# OUT_MOT.net
KiCad netlist of a schematic drawn in Altium Designer
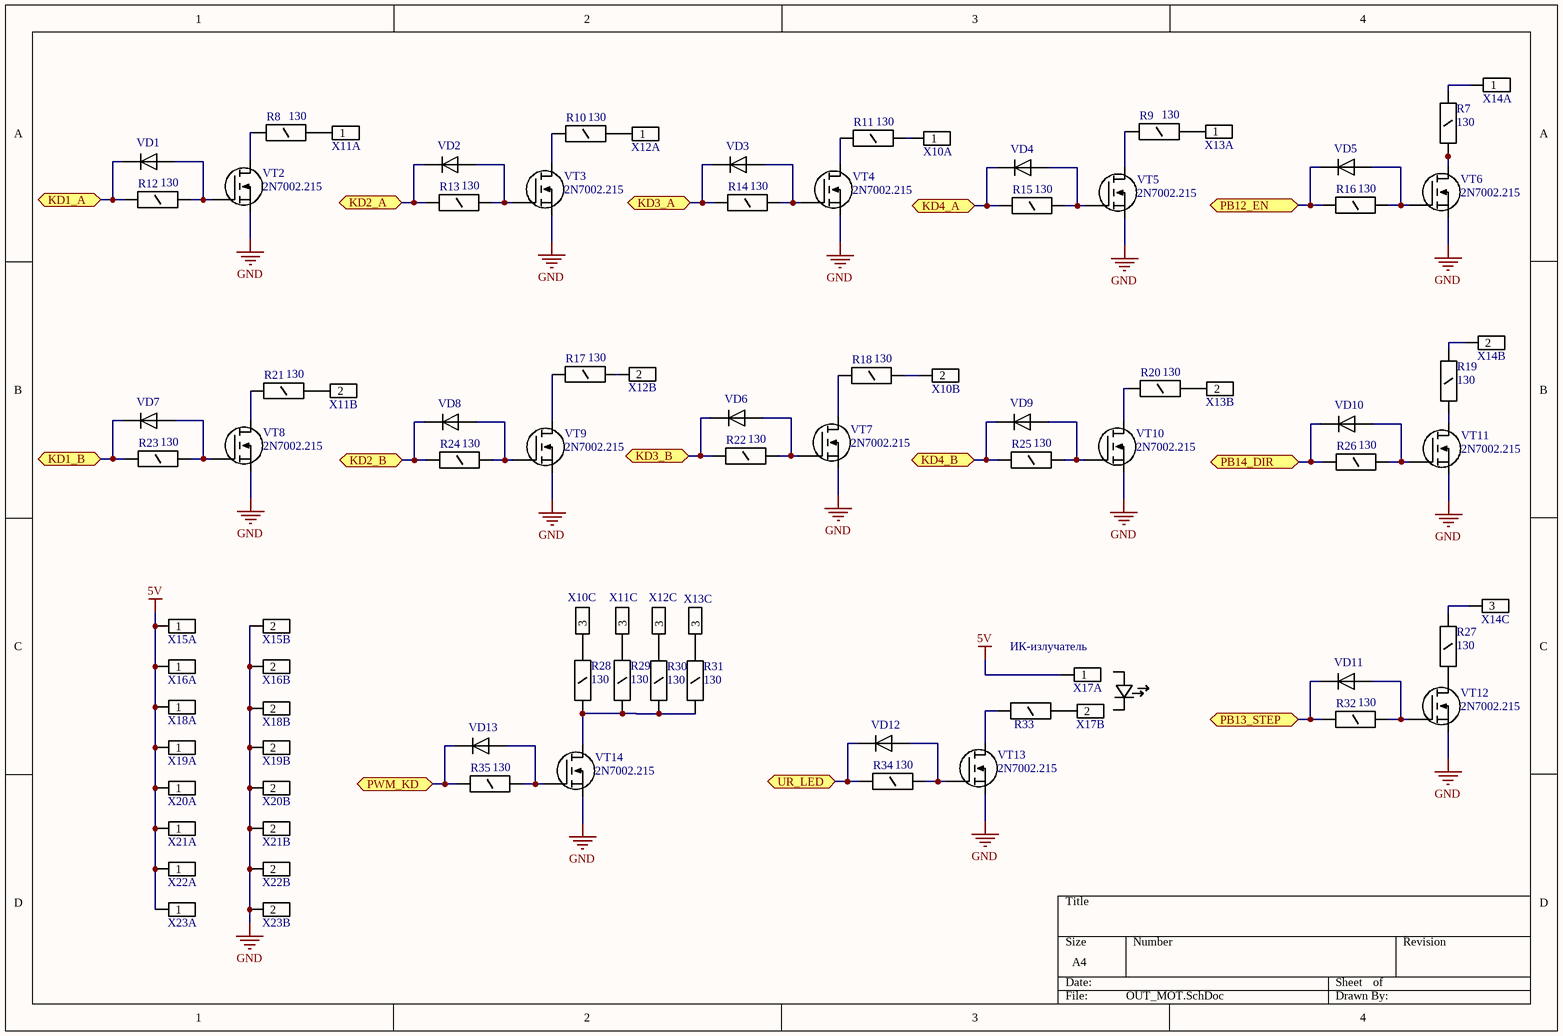
[diagram p0: OUT_MOT.SchDoc]

(export (version "E")
  (design (tool "Eeschema 10.0.6"))
  (components
    (comp (ref "R7")
      (value "130")
      (footprint "R_1206")
      (description "0,25 Вт")
      (fields (field (name "POWER") "0.25 Вт") (field (name "TOLERANCE") "5%"))
      (libsource (lib "") (part "Резистор 1206_1"))
    )
    (comp (ref "R8")
      (value "130")
      (footprint "R_1206")
      (description "0,25 Вт")
      (fields (field (name "POWER") "0.25 Вт") (field (name "TOLERANCE") "5%"))
      (libsource (lib "Res_end_Cap") (part "Резистор 1206"))
    )
    (comp (ref "R9")
      (value "130")
      (footprint "R_1206")
      (description "0,25 Вт")
      (fields (field (name "POWER") "0.25 Вт") (field (name "TOLERANCE") "5%"))
      (libsource (lib "Res_end_Cap") (part "Резистор 1206"))
    )
    (comp (ref "R10")
      (value "130")
      (footprint "R_1206")
      (description "0,25 Вт")
      (fields (field (name "POWER") "0.25 Вт") (field (name "TOLERANCE") "5%"))
      (libsource (lib "Res_end_Cap") (part "Резистор 1206"))
    )
    (comp (ref "R11")
      (value "130")
      (footprint "R_1206")
      (description "0,25 Вт")
      (fields (field (name "POWER") "0.25 Вт") (field (name "TOLERANCE") "5%"))
      (libsource (lib "Res_end_Cap") (part "Резистор 1206"))
    )
    (comp (ref "R12")
      (value "130")
      (footprint "R_1206")
      (description "0,25 Вт")
      (fields (field (name "POWER") "0.25 Вт") (field (name "TOLERANCE") "5%"))
      (libsource (lib "Res_end_Cap") (part "Резистор 1206"))
    )
    (comp (ref "R13")
      (value "130")
      (footprint "R_1206")
      (description "0,25 Вт")
      (fields (field (name "POWER") "0.25 Вт") (field (name "TOLERANCE") "5%"))
      (libsource (lib "Res_end_Cap") (part "Резистор 1206"))
    )
    (comp (ref "R14")
      (value "130")
      (footprint "R_1206")
      (description "0,25 Вт")
      (fields (field (name "POWER") "0.25 Вт") (field (name "TOLERANCE") "5%"))
      (libsource (lib "Res_end_Cap") (part "Резистор 1206"))
    )
    (comp (ref "R15")
      (value "130")
      (footprint "R_1206")
      (description "0,25 Вт")
      (fields (field (name "POWER") "0.25 Вт") (field (name "TOLERANCE") "5%"))
      (libsource (lib "Res_end_Cap") (part "Резистор 1206"))
    )
    (comp (ref "R16")
      (value "130")
      (footprint "R_1206")
      (description "0,25 Вт")
      (fields (field (name "POWER") "0.25 Вт") (field (name "TOLERANCE") "5%"))
      (libsource (lib "Res_end_Cap") (part "Резистор 1206"))
    )
    (comp (ref "R17")
      (value "130")
      (footprint "R_1206")
      (description "0,25 Вт")
      (fields (field (name "POWER") "0.25 Вт") (field (name "TOLERANCE") "5%"))
      (libsource (lib "Res_end_Cap") (part "Резистор 1206"))
    )
    (comp (ref "R18")
      (value "130")
      (footprint "R_1206")
      (description "0,25 Вт")
      (fields (field (name "POWER") "0.25 Вт") (field (name "TOLERANCE") "5%"))
      (libsource (lib "Res_end_Cap") (part "Резистор 1206"))
    )
    (comp (ref "R19")
      (value "130")
      (footprint "R_1206")
      (description "0,25 Вт")
      (fields (field (name "POWER") "0.25 Вт") (field (name "TOLERANCE") "5%"))
      (libsource (lib "") (part "Резистор 1206_1"))
    )
    (comp (ref "R20")
      (value "130")
      (footprint "R_1206")
      (description "0,25 Вт")
      (fields (field (name "POWER") "0.25 Вт") (field (name "TOLERANCE") "5%"))
      (libsource (lib "Res_end_Cap") (part "Резистор 1206"))
    )
    (comp (ref "R21")
      (value "130")
      (footprint "R_1206")
      (description "0,25 Вт")
      (fields (field (name "POWER") "0.25 Вт") (field (name "TOLERANCE") "5%"))
      (libsource (lib "Res_end_Cap") (part "Резистор 1206"))
    )
    (comp (ref "R22")
      (value "130")
      (footprint "R_1206")
      (description "0,25 Вт")
      (fields (field (name "POWER") "0.25 Вт") (field (name "TOLERANCE") "5%"))
      (libsource (lib "Res_end_Cap") (part "Резистор 1206"))
    )
    (comp (ref "R23")
      (value "130")
      (footprint "R_1206")
      (description "0,25 Вт")
      (fields (field (name "POWER") "0.25 Вт") (field (name "TOLERANCE") "5%"))
      (libsource (lib "Res_end_Cap") (part "Резистор 1206"))
    )
    (comp (ref "R24")
      (value "130")
      (footprint "R_1206")
      (description "0,25 Вт")
      (fields (field (name "POWER") "0.25 Вт") (field (name "TOLERANCE") "5%"))
      (libsource (lib "Res_end_Cap") (part "Резистор 1206"))
    )
    (comp (ref "R25")
      (value "130")
      (footprint "R_1206")
      (description "0,25 Вт")
      (fields (field (name "POWER") "0.25 Вт") (field (name "TOLERANCE") "5%"))
      (libsource (lib "Res_end_Cap") (part "Резистор 1206"))
    )
    (comp (ref "R26")
      (value "130")
      (footprint "R_1206")
      (description "0,25 Вт")
      (fields (field (name "POWER") "0.25 Вт") (field (name "TOLERANCE") "5%"))
      (libsource (lib "Res_end_Cap") (part "Резистор 1206"))
    )
    (comp (ref "R27")
      (value "130")
      (footprint "R_1206")
      (description "0,25 Вт")
      (fields (field (name "POWER") "0.25 Вт") (field (name "TOLERANCE") "5%"))
      (libsource (lib "") (part "Резистор 1206_1"))
    )
    (comp (ref "R28")
      (value "130")
      (footprint "R_1206")
      (description "0,25 Вт")
      (fields (field (name "POWER") "0.25 Вт") (field (name "TOLERANCE") "5%"))
      (libsource (lib "") (part "Резистор 1206_1"))
    )
    (comp (ref "R29")
      (value "130")
      (footprint "R_1206")
      (description "0,25 Вт")
      (fields (field (name "POWER") "0.25 Вт") (field (name "TOLERANCE") "5%"))
      (libsource (lib "") (part "Резистор 1206_1"))
    )
    (comp (ref "R30")
      (value "130")
      (footprint "R_1206")
      (description "0,25 Вт")
      (fields (field (name "POWER") "0.25 Вт") (field (name "TOLERANCE") "5%"))
      (libsource (lib "") (part "Резистор 1206_1"))
    )
    (comp (ref "R31")
      (value "130")
      (footprint "R_1206")
      (description "0,25 Вт")
      (fields (field (name "POWER") "0.25 Вт") (field (name "TOLERANCE") "5%"))
      (libsource (lib "") (part "Резистор 1206_1"))
    )
    (comp (ref "R32")
      (value "130")
      (footprint "R_1206")
      (description "0,25 Вт")
      (fields (field (name "POWER") "0.25 Вт") (field (name "TOLERANCE") "5%"))
      (libsource (lib "Res_end_Cap") (part "Резистор 1206"))
    )
    (comp (ref "R33")
      (value "0")
      (footprint "R_1206")
      (description "0,25 Вт")
      (fields (field (name "POWER") "0.25 Вт") (field (name "TOLERANCE") "5%"))
      (libsource (lib "") (part "Резистор 1206_2"))
    )
    (comp (ref "R34")
      (value "130")
      (footprint "R_1206")
      (description "0,25 Вт")
      (fields (field (name "POWER") "0.25 Вт") (field (name "TOLERANCE") "5%"))
      (libsource (lib "Res_end_Cap") (part "Резистор 1206"))
    )
    (comp (ref "R35")
      (value "130")
      (footprint "R_1206")
      (description "0,25 Вт")
      (fields (field (name "POWER") "0.25 Вт") (field (name "TOLERANCE") "5%"))
      (libsource (lib "Res_end_Cap") (part "Резистор 1206"))
    )
    (comp (ref "VD1")
      (value "MBR0520LT1G")
      (footprint "SOD-123")
      (description "диод, SMD")
      (libsource (lib "Диоды и транзисторы") (part "SMA400*"))
    )
    (comp (ref "VD2")
      (value "MBR0520LT1G")
      (footprint "SOD-123")
      (description "диод, SMD")
      (libsource (lib "Диоды и транзисторы") (part "SMA400*"))
    )
    (comp (ref "VD3")
      (value "MBR0520LT1G")
      (footprint "SOD-123")
      (description "диод, SMD")
      (libsource (lib "Диоды и транзисторы") (part "SMA400*"))
    )
    (comp (ref "VD4")
      (value "MBR0520LT1G")
      (footprint "SOD-123")
      (description "диод, SMD")
      (libsource (lib "Диоды и транзисторы") (part "SMA400*"))
    )
    (comp (ref "VD5")
      (value "MBR0520LT1G")
      (footprint "SOD-123")
      (description "диод, SMD")
      (libsource (lib "Диоды и транзисторы") (part "SMA400*"))
    )
    (comp (ref "VD6")
      (value "MBR0520LT1G")
      (footprint "SOD-123")
      (description "диод, SMD")
      (libsource (lib "Диоды и транзисторы") (part "SMA400*"))
    )
    (comp (ref "VD7")
      (value "MBR0520LT1G")
      (footprint "SOD-123")
      (description "диод, SMD")
      (libsource (lib "Диоды и транзисторы") (part "SMA400*"))
    )
    (comp (ref "VD8")
      (value "MBR0520LT1G")
      (footprint "SOD-123")
      (description "диод, SMD")
      (libsource (lib "Диоды и транзисторы") (part "SMA400*"))
    )
    (comp (ref "VD9")
      (value "MBR0520LT1G")
      (footprint "SOD-123")
      (description "диод, SMD")
      (libsource (lib "Диоды и транзисторы") (part "SMA400*"))
    )
    (comp (ref "VD10")
      (value "MBR0520LT1G")
      (footprint "SOD-123")
      (description "диод, SMD")
      (libsource (lib "Диоды и транзисторы") (part "SMA400*"))
    )
    (comp (ref "VD11")
      (value "MBR0520LT1G")
      (footprint "SOD-123")
      (description "диод, SMD")
      (libsource (lib "Диоды и транзисторы") (part "SMA400*"))
    )
    (comp (ref "VD12")
      (value "MBR0520LT1G")
      (footprint "SOD-123")
      (description "диод, SMD")
      (libsource (lib "Диоды и транзисторы") (part "SMA400*"))
    )
    (comp (ref "VD13")
      (value "MBR0520LT1G")
      (footprint "SOD-123")
      (description "диод, SMD")
      (libsource (lib "Диоды и транзисторы") (part "SMA400*"))
    )
    (comp (ref "VT2")
      (value "2N7002.215")
      (footprint "SOT23")
      (description "MOSFET, SOT23")
      (libsource (lib "Диоды и транзисторы") (part "2N7002.215"))
    )
    (comp (ref "VT3")
      (value "2N7002.215")
      (footprint "SOT23")
      (description "MOSFET, SOT23")
      (libsource (lib "Диоды и транзисторы") (part "2N7002.215"))
    )
    (comp (ref "VT4")
      (value "2N7002.215")
      (footprint "SOT23")
      (description "MOSFET, SOT23")
      (libsource (lib "Диоды и транзисторы") (part "2N7002.215"))
    )
    (comp (ref "VT5")
      (value "2N7002.215")
      (footprint "SOT23")
      (description "MOSFET, SOT23")
      (libsource (lib "Диоды и транзисторы") (part "2N7002.215"))
    )
    (comp (ref "VT6")
      (value "2N7002.215")
      (footprint "SOT23")
      (description "MOSFET, SOT23")
      (libsource (lib "Диоды и транзисторы") (part "2N7002.215"))
    )
    (comp (ref "VT7")
      (value "2N7002.215")
      (footprint "SOT23")
      (description "MOSFET, SOT23")
      (libsource (lib "Диоды и транзисторы") (part "2N7002.215"))
    )
    (comp (ref "VT8")
      (value "2N7002.215")
      (footprint "SOT23")
      (description "MOSFET, SOT23")
      (libsource (lib "Диоды и транзисторы") (part "2N7002.215"))
    )
    (comp (ref "VT9")
      (value "2N7002.215")
      (footprint "SOT23")
      (description "MOSFET, SOT23")
      (libsource (lib "Диоды и транзисторы") (part "2N7002.215"))
    )
    (comp (ref "VT10")
      (value "2N7002.215")
      (footprint "SOT23")
      (description "MOSFET, SOT23")
      (libsource (lib "Диоды и транзисторы") (part "2N7002.215"))
    )
    (comp (ref "VT11")
      (value "2N7002.215")
      (footprint "SOT23")
      (description "MOSFET, SOT23")
      (libsource (lib "Диоды и транзисторы") (part "2N7002.215"))
    )
    (comp (ref "VT12")
      (value "2N7002.215")
      (footprint "SOT23")
      (description "MOSFET, SOT23")
      (libsource (lib "Диоды и транзисторы") (part "2N7002.215"))
    )
    (comp (ref "VT13")
      (value "2N7002.215")
      (footprint "SOT23")
      (description "MOSFET, SOT23")
      (libsource (lib "Диоды и транзисторы") (part "2N7002.215"))
    )
    (comp (ref "VT14")
      (value "2N7002.215")
      (footprint "SOT23")
      (description "MOSFET, SOT23")
      (libsource (lib "Диоды и транзисторы") (part "2N7002.215"))
    )
    (comp (ref "X10")
      (value "300-031-12")
      (footprint "300-031-12")
      (description "клеммник винтовой 3к.,5мм")
      (libsource (lib "Klemniki") (part "300-031-12"))
    )
    (comp (ref "X11")
      (value "300-031-12")
      (footprint "300-031-12")
      (description "клеммник винтовой 3к.,5мм")
      (libsource (lib "Klemniki") (part "300-031-12"))
    )
    (comp (ref "X12")
      (value "300-031-12")
      (footprint "300-031-12")
      (description "клеммник винтовой 3к.,5мм")
      (libsource (lib "Klemniki") (part "300-031-12"))
    )
    (comp (ref "X13")
      (value "300-031-12")
      (footprint "300-031-12")
      (description "клеммник винтовой 3к.,5мм")
      (libsource (lib "Klemniki") (part "300-031-12"))
    )
    (comp (ref "X14")
      (value "300-031-12")
      (footprint "300-031-12")
      (description "клеммник винтовой 3к.,5мм")
      (libsource (lib "Klemniki") (part "300-031-12"))
    )
    (comp (ref "X15")
      (value "DG508V-02")
      (footprint "DG508V-02")
      (description "клеммник винтовой 2к.,5.08мм")
      (libsource (lib "Klemniki") (part "DG508V-02"))
    )
    (comp (ref "X16")
      (value "DG508V-02")
      (footprint "DG508V-02")
      (description "клеммник винтовой 2к.,5.08мм")
      (libsource (lib "Klemniki") (part "DG508V-02"))
    )
    (comp (ref "X17")
      (value "DG508V-02")
      (footprint "DG508V-02")
      (description "клеммник винтовой 2к.,5.08мм")
      (libsource (lib "Klemniki") (part "DG508V-02"))
    )
    (comp (ref "X18")
      (value "DG508V-02")
      (footprint "DG508V-02")
      (description "клеммник винтовой 2к.,5.08мм")
      (libsource (lib "Klemniki") (part "DG508V-02"))
    )
    (comp (ref "X19")
      (value "DG508V-02")
      (footprint "DG508V-02")
      (description "клеммник винтовой 2к.,5.08мм")
      (libsource (lib "Klemniki") (part "DG508V-02"))
    )
    (comp (ref "X20")
      (value "DG508V-02")
      (footprint "DG508V-02")
      (description "клеммник винтовой 2к.,5.08мм")
      (libsource (lib "Klemniki") (part "DG508V-02"))
    )
    (comp (ref "X21")
      (value "DG508V-02")
      (footprint "DG508V-02")
      (description "клеммник винтовой 2к.,5.08мм")
      (libsource (lib "Klemniki") (part "DG508V-02"))
    )
    (comp (ref "X22")
      (value "DG508V-02")
      (footprint "DG508V-02")
      (description "клеммник винтовой 2к.,5.08мм")
      (libsource (lib "Klemniki") (part "DG508V-02"))
    )
    (comp (ref "X23")
      (value "DG508V-02")
      (footprint "DG508V-02")
      (description "клеммник винтовой 2к.,5.08мм")
      (libsource (lib "Klemniki") (part "DG508V-02"))
    )
  )
  (nets
    (net (code "1") (name "/KD1_A") (class "Default")
      (node (ref "R12") (pin "1") (pinfunction "1_1") (pintype "passive"))
      (node (ref "VD1") (pin "K") (pinfunction "K_K") (pintype "passive"))
    )
    (net (code "2") (name "/KD1_B") (class "Default")
      (node (ref "R23") (pin "1") (pinfunction "1_1") (pintype "passive"))
      (node (ref "VD7") (pin "K") (pinfunction "K_K") (pintype "passive"))
    )
    (net (code "3") (name "/KD2_A") (class "Default")
      (node (ref "R13") (pin "1") (pinfunction "1_1") (pintype "passive"))
      (node (ref "VD2") (pin "K") (pinfunction "K_K") (pintype "passive"))
    )
    (net (code "4") (name "/KD2_B") (class "Default")
      (node (ref "R24") (pin "1") (pinfunction "1_1") (pintype "passive"))
      (node (ref "VD8") (pin "K") (pinfunction "K_K") (pintype "passive"))
    )
    (net (code "5") (name "/KD3_A") (class "Default")
      (node (ref "R14") (pin "1") (pinfunction "1_1") (pintype "passive"))
      (node (ref "VD3") (pin "K") (pinfunction "K_K") (pintype "passive"))
    )
    (net (code "6") (name "/KD3_B") (class "Default")
      (node (ref "R22") (pin "1") (pinfunction "1_1") (pintype "passive"))
      (node (ref "VD6") (pin "K") (pinfunction "K_K") (pintype "passive"))
    )
    (net (code "7") (name "/KD4_A") (class "Default")
      (node (ref "R15") (pin "1") (pinfunction "1_1") (pintype "passive"))
      (node (ref "VD4") (pin "K") (pinfunction "K_K") (pintype "passive"))
    )
    (net (code "8") (name "/KD4_B") (class "Default")
      (node (ref "R25") (pin "1") (pinfunction "1_1") (pintype "passive"))
      (node (ref "VD9") (pin "K") (pinfunction "K_K") (pintype "passive"))
    )
    (net (code "9") (name "/PB12_EN") (class "Default")
      (node (ref "R16") (pin "1") (pinfunction "1_1") (pintype "passive"))
      (node (ref "VD5") (pin "K") (pinfunction "K_K") (pintype "passive"))
    )
    (net (code "10") (name "/PB13_STEP") (class "Default")
      (node (ref "R32") (pin "1") (pinfunction "1_1") (pintype "passive"))
      (node (ref "VD11") (pin "K") (pinfunction "K_K") (pintype "passive"))
    )
    (net (code "11") (name "/PB14_DIR") (class "Default")
      (node (ref "R26") (pin "1") (pinfunction "1_1") (pintype "passive"))
      (node (ref "VD10") (pin "K") (pinfunction "K_K") (pintype "passive"))
    )
    (net (code "12") (name "/PWM_KD") (class "Default")
      (node (ref "R35") (pin "1") (pinfunction "1_1") (pintype "passive"))
      (node (ref "VD13") (pin "K") (pinfunction "K_K") (pintype "passive"))
    )
    (net (code "13") (name "/UR_LED") (class "Default")
      (node (ref "R34") (pin "1") (pinfunction "1_1") (pintype "passive"))
      (node (ref "VD12") (pin "K") (pinfunction "K_K") (pintype "passive"))
    )
    (net (code "14") (name "5V") (class "Default")
      (node (ref "X15") (pin "1") (pinfunction "1_1") (pintype "passive"))
      (node (ref "X16") (pin "1") (pinfunction "1_1") (pintype "passive"))
      (node (ref "X17") (pin "1") (pinfunction "1_1") (pintype "passive"))
      (node (ref "X18") (pin "1") (pinfunction "1_1") (pintype "passive"))
      (node (ref "X19") (pin "1") (pinfunction "1_1") (pintype "passive"))
      (node (ref "X20") (pin "1") (pinfunction "1_1") (pintype "passive"))
      (node (ref "X21") (pin "1") (pinfunction "1_1") (pintype "passive"))
      (node (ref "X22") (pin "1") (pinfunction "1_1") (pintype "passive"))
      (node (ref "X23") (pin "1") (pinfunction "1_1") (pintype "passive"))
    )
    (net (code "15") (name "GND") (class "Default")
      (node (ref "VT10") (pin "2") (pinfunction "S_2") (pintype "passive"))
      (node (ref "VT11") (pin "2") (pinfunction "S_2") (pintype "passive"))
      (node (ref "VT12") (pin "2") (pinfunction "S_2") (pintype "passive"))
      (node (ref "VT13") (pin "2") (pinfunction "S_2") (pintype "passive"))
      (node (ref "VT14") (pin "2") (pinfunction "S_2") (pintype "passive"))
      (node (ref "VT2") (pin "2") (pinfunction "S_2") (pintype "passive"))
      (node (ref "VT3") (pin "2") (pinfunction "S_2") (pintype "passive"))
      (node (ref "VT4") (pin "2") (pinfunction "S_2") (pintype "passive"))
      (node (ref "VT5") (pin "2") (pinfunction "S_2") (pintype "passive"))
      (node (ref "VT6") (pin "2") (pinfunction "S_2") (pintype "passive"))
      (node (ref "VT7") (pin "2") (pinfunction "S_2") (pintype "passive"))
      (node (ref "VT8") (pin "2") (pinfunction "S_2") (pintype "passive"))
      (node (ref "VT9") (pin "2") (pinfunction "S_2") (pintype "passive"))
      (node (ref "X15") (pin "2") (pinfunction "2_2") (pintype "passive"))
      (node (ref "X16") (pin "2") (pinfunction "2_2") (pintype "passive"))
      (node (ref "X18") (pin "2") (pinfunction "2_2") (pintype "passive"))
      (node (ref "X19") (pin "2") (pinfunction "2_2") (pintype "passive"))
      (node (ref "X20") (pin "2") (pinfunction "2_2") (pintype "passive"))
      (node (ref "X21") (pin "2") (pinfunction "2_2") (pintype "passive"))
      (node (ref "X22") (pin "2") (pinfunction "2_2") (pintype "passive"))
      (node (ref "X23") (pin "2") (pinfunction "2_2") (pintype "passive"))
    )
    (net (code "16") (name "Net-(R7-Pad2)") (class "Default")
      (node (ref "R7") (pin "2") (pinfunction "2_2") (pintype "passive"))
      (node (ref "X14") (pin "1") (pinfunction "1_1") (pintype "passive"))
    )
    (net (code "17") (name "Net-(R8-Pad2)") (class "Default")
      (node (ref "R8") (pin "2") (pinfunction "2_2") (pintype "passive"))
      (node (ref "X11") (pin "1") (pinfunction "1_1") (pintype "passive"))
    )
    (net (code "18") (name "Net-(R9-Pad2)") (class "Default")
      (node (ref "R9") (pin "2") (pinfunction "2_2") (pintype "passive"))
      (node (ref "X13") (pin "1") (pinfunction "1_1") (pintype "passive"))
    )
    (net (code "19") (name "Net-(R10-Pad2)") (class "Default")
      (node (ref "R10") (pin "2") (pinfunction "2_2") (pintype "passive"))
      (node (ref "X12") (pin "1") (pinfunction "1_1") (pintype "passive"))
    )
    (net (code "20") (name "Net-(R11-Pad2)") (class "Default")
      (node (ref "R11") (pin "2") (pinfunction "2_2") (pintype "passive"))
      (node (ref "X10") (pin "1") (pinfunction "1_1") (pintype "passive"))
    )
    (net (code "21") (name "Net-(R17-Pad2)") (class "Default")
      (node (ref "R17") (pin "2") (pinfunction "2_2") (pintype "passive"))
      (node (ref "X12") (pin "2") (pinfunction "2_2") (pintype "passive"))
    )
    (net (code "22") (name "Net-(R18-Pad2)") (class "Default")
      (node (ref "R18") (pin "2") (pinfunction "2_2") (pintype "passive"))
      (node (ref "X10") (pin "2") (pinfunction "2_2") (pintype "passive"))
    )
    (net (code "23") (name "Net-(R19-Pad2)") (class "Default")
      (node (ref "R19") (pin "2") (pinfunction "2_2") (pintype "passive"))
      (node (ref "X14") (pin "2") (pinfunction "2_2") (pintype "passive"))
    )
    (net (code "24") (name "Net-(R20-Pad2)") (class "Default")
      (node (ref "R20") (pin "2") (pinfunction "2_2") (pintype "passive"))
      (node (ref "X13") (pin "2") (pinfunction "2_2") (pintype "passive"))
    )
    (net (code "25") (name "Net-(R21-Pad2)") (class "Default")
      (node (ref "R21") (pin "2") (pinfunction "2_2") (pintype "passive"))
      (node (ref "X11") (pin "2") (pinfunction "2_2") (pintype "passive"))
    )
    (net (code "26") (name "Net-(R27-Pad2)") (class "Default")
      (node (ref "R27") (pin "2") (pinfunction "2_2") (pintype "passive"))
      (node (ref "X14") (pin "3") (pinfunction "3_3") (pintype "passive"))
    )
    (net (code "27") (name "Net-(R28-Pad2)") (class "Default")
      (node (ref "R28") (pin "2") (pinfunction "2_2") (pintype "passive"))
      (node (ref "X10") (pin "3") (pinfunction "3_3") (pintype "passive"))
    )
    (net (code "28") (name "Net-(R29-Pad2)") (class "Default")
      (node (ref "R29") (pin "2") (pinfunction "2_2") (pintype "passive"))
      (node (ref "X11") (pin "3") (pinfunction "3_3") (pintype "passive"))
    )
    (net (code "29") (name "Net-(R30-Pad2)") (class "Default")
      (node (ref "R30") (pin "2") (pinfunction "2_2") (pintype "passive"))
      (node (ref "X12") (pin "3") (pinfunction "3_3") (pintype "passive"))
    )
    (net (code "30") (name "Net-(R31-Pad2)") (class "Default")
      (node (ref "R31") (pin "2") (pinfunction "2_2") (pintype "passive"))
      (node (ref "X13") (pin "3") (pinfunction "3_3") (pintype "passive"))
    )
    (net (code "31") (name "Net-(R33-Pad1)") (class "Default")
      (node (ref "R33") (pin "1") (pinfunction "1_1") (pintype "passive"))
      (node (ref "X17") (pin "2") (pinfunction "2_2") (pintype "passive"))
    )
    (net (code "32") (name "Net-(VT2-D)") (class "Default")
      (node (ref "R8") (pin "1") (pinfunction "1_1") (pintype "passive"))
      (node (ref "VT2") (pin "3") (pinfunction "D_3") (pintype "passive"))
    )
    (net (code "33") (name "Net-(VT2-G)") (class "Default")
      (node (ref "R12") (pin "2") (pinfunction "2_2") (pintype "passive"))
      (node (ref "VD1") (pin "A") (pinfunction "A_A") (pintype "passive"))
      (node (ref "VT2") (pin "1") (pinfunction "G_1") (pintype "passive"))
    )
    (net (code "34") (name "Net-(VT3-D)") (class "Default")
      (node (ref "R10") (pin "1") (pinfunction "1_1") (pintype "passive"))
      (node (ref "VT3") (pin "3") (pinfunction "D_3") (pintype "passive"))
    )
    (net (code "35") (name "Net-(VT3-G)") (class "Default")
      (node (ref "R13") (pin "2") (pinfunction "2_2") (pintype "passive"))
      (node (ref "VD2") (pin "A") (pinfunction "A_A") (pintype "passive"))
      (node (ref "VT3") (pin "1") (pinfunction "G_1") (pintype "passive"))
    )
    (net (code "36") (name "Net-(VT4-D)") (class "Default")
      (node (ref "R11") (pin "1") (pinfunction "1_1") (pintype "passive"))
      (node (ref "VT4") (pin "3") (pinfunction "D_3") (pintype "passive"))
    )
    (net (code "37") (name "Net-(VT4-G)") (class "Default")
      (node (ref "R14") (pin "2") (pinfunction "2_2") (pintype "passive"))
      (node (ref "VD3") (pin "A") (pinfunction "A_A") (pintype "passive"))
      (node (ref "VT4") (pin "1") (pinfunction "G_1") (pintype "passive"))
    )
    (net (code "38") (name "Net-(VT5-D)") (class "Default")
      (node (ref "R9") (pin "1") (pinfunction "1_1") (pintype "passive"))
      (node (ref "VT5") (pin "3") (pinfunction "D_3") (pintype "passive"))
    )
    (net (code "39") (name "Net-(VT5-G)") (class "Default")
      (node (ref "R15") (pin "2") (pinfunction "2_2") (pintype "passive"))
      (node (ref "VD4") (pin "A") (pinfunction "A_A") (pintype "passive"))
      (node (ref "VT5") (pin "1") (pinfunction "G_1") (pintype "passive"))
    )
    (net (code "40") (name "Net-(VT6-D)") (class "Default")
      (node (ref "R7") (pin "1") (pinfunction "1_1") (pintype "passive"))
      (node (ref "VT6") (pin "3") (pinfunction "D_3") (pintype "passive"))
    )
    (net (code "41") (name "Net-(VT6-G)") (class "Default")
      (node (ref "R16") (pin "2") (pinfunction "2_2") (pintype "passive"))
      (node (ref "VD5") (pin "A") (pinfunction "A_A") (pintype "passive"))
      (node (ref "VT6") (pin "1") (pinfunction "G_1") (pintype "passive"))
    )
    (net (code "42") (name "Net-(VT7-D)") (class "Default")
      (node (ref "R18") (pin "1") (pinfunction "1_1") (pintype "passive"))
      (node (ref "VT7") (pin "3") (pinfunction "D_3") (pintype "passive"))
    )
    (net (code "43") (name "Net-(VT7-G)") (class "Default")
      (node (ref "R22") (pin "2") (pinfunction "2_2") (pintype "passive"))
      (node (ref "VD6") (pin "A") (pinfunction "A_A") (pintype "passive"))
      (node (ref "VT7") (pin "1") (pinfunction "G_1") (pintype "passive"))
    )
    (net (code "44") (name "Net-(VT8-D)") (class "Default")
      (node (ref "R21") (pin "1") (pinfunction "1_1") (pintype "passive"))
      (node (ref "VT8") (pin "3") (pinfunction "D_3") (pintype "passive"))
    )
    (net (code "45") (name "Net-(VT8-G)") (class "Default")
      (node (ref "R23") (pin "2") (pinfunction "2_2") (pintype "passive"))
      (node (ref "VD7") (pin "A") (pinfunction "A_A") (pintype "passive"))
      (node (ref "VT8") (pin "1") (pinfunction "G_1") (pintype "passive"))
    )
    (net (code "46") (name "Net-(VT9-D)") (class "Default")
      (node (ref "R17") (pin "1") (pinfunction "1_1") (pintype "passive"))
      (node (ref "VT9") (pin "3") (pinfunction "D_3") (pintype "passive"))
    )
    (net (code "47") (name "Net-(VT9-G)") (class "Default")
      (node (ref "R24") (pin "2") (pinfunction "2_2") (pintype "passive"))
      (node (ref "VD8") (pin "A") (pinfunction "A_A") (pintype "passive"))
      (node (ref "VT9") (pin "1") (pinfunction "G_1") (pintype "passive"))
    )
    (net (code "48") (name "Net-(VT10-D)") (class "Default")
      (node (ref "R20") (pin "1") (pinfunction "1_1") (pintype "passive"))
      (node (ref "VT10") (pin "3") (pinfunction "D_3") (pintype "passive"))
    )
    (net (code "49") (name "Net-(VT10-G)") (class "Default")
      (node (ref "R25") (pin "2") (pinfunction "2_2") (pintype "passive"))
      (node (ref "VD9") (pin "A") (pinfunction "A_A") (pintype "passive"))
      (node (ref "VT10") (pin "1") (pinfunction "G_1") (pintype "passive"))
    )
    (net (code "50") (name "Net-(VT11-D)") (class "Default")
      (node (ref "R19") (pin "1") (pinfunction "1_1") (pintype "passive"))
      (node (ref "VT11") (pin "3") (pinfunction "D_3") (pintype "passive"))
    )
    (net (code "51") (name "Net-(VT11-G)") (class "Default")
      (node (ref "R26") (pin "2") (pinfunction "2_2") (pintype "passive"))
      (node (ref "VD10") (pin "A") (pinfunction "A_A") (pintype "passive"))
      (node (ref "VT11") (pin "1") (pinfunction "G_1") (pintype "passive"))
    )
    (net (code "52") (name "Net-(VT12-D)") (class "Default")
      (node (ref "R27") (pin "1") (pinfunction "1_1") (pintype "passive"))
      (node (ref "VT12") (pin "3") (pinfunction "D_3") (pintype "passive"))
    )
    (net (code "53") (name "Net-(VT12-G)") (class "Default")
      (node (ref "R32") (pin "2") (pinfunction "2_2") (pintype "passive"))
      (node (ref "VD11") (pin "A") (pinfunction "A_A") (pintype "passive"))
      (node (ref "VT12") (pin "1") (pinfunction "G_1") (pintype "passive"))
    )
    (net (code "54") (name "Net-(VT13-D)") (class "Default")
      (node (ref "R33") (pin "2") (pinfunction "2_2") (pintype "passive"))
      (node (ref "VT13") (pin "3") (pinfunction "D_3") (pintype "passive"))
    )
    (net (code "55") (name "Net-(VT13-G)") (class "Default")
      (node (ref "R34") (pin "2") (pinfunction "2_2") (pintype "passive"))
      (node (ref "VD12") (pin "A") (pinfunction "A_A") (pintype "passive"))
      (node (ref "VT13") (pin "1") (pinfunction "G_1") (pintype "passive"))
    )
    (net (code "56") (name "Net-(VT14-D)") (class "Default")
      (node (ref "R28") (pin "1") (pinfunction "1_1") (pintype "passive"))
      (node (ref "R29") (pin "1") (pinfunction "1_1") (pintype "passive"))
      (node (ref "R30") (pin "1") (pinfunction "1_1") (pintype "passive"))
      (node (ref "R31") (pin "1") (pinfunction "1_1") (pintype "passive"))
      (node (ref "VT14") (pin "3") (pinfunction "D_3") (pintype "passive"))
    )
    (net (code "57") (name "Net-(VT14-G)") (class "Default")
      (node (ref "R35") (pin "2") (pinfunction "2_2") (pintype "passive"))
      (node (ref "VD13") (pin "A") (pinfunction "A_A") (pintype "passive"))
      (node (ref "VT14") (pin "1") (pinfunction "G_1") (pintype "passive"))
    )
  )
)
